# 01_MCU.net
KiCad netlist of a schematic drawn in Altium Designer
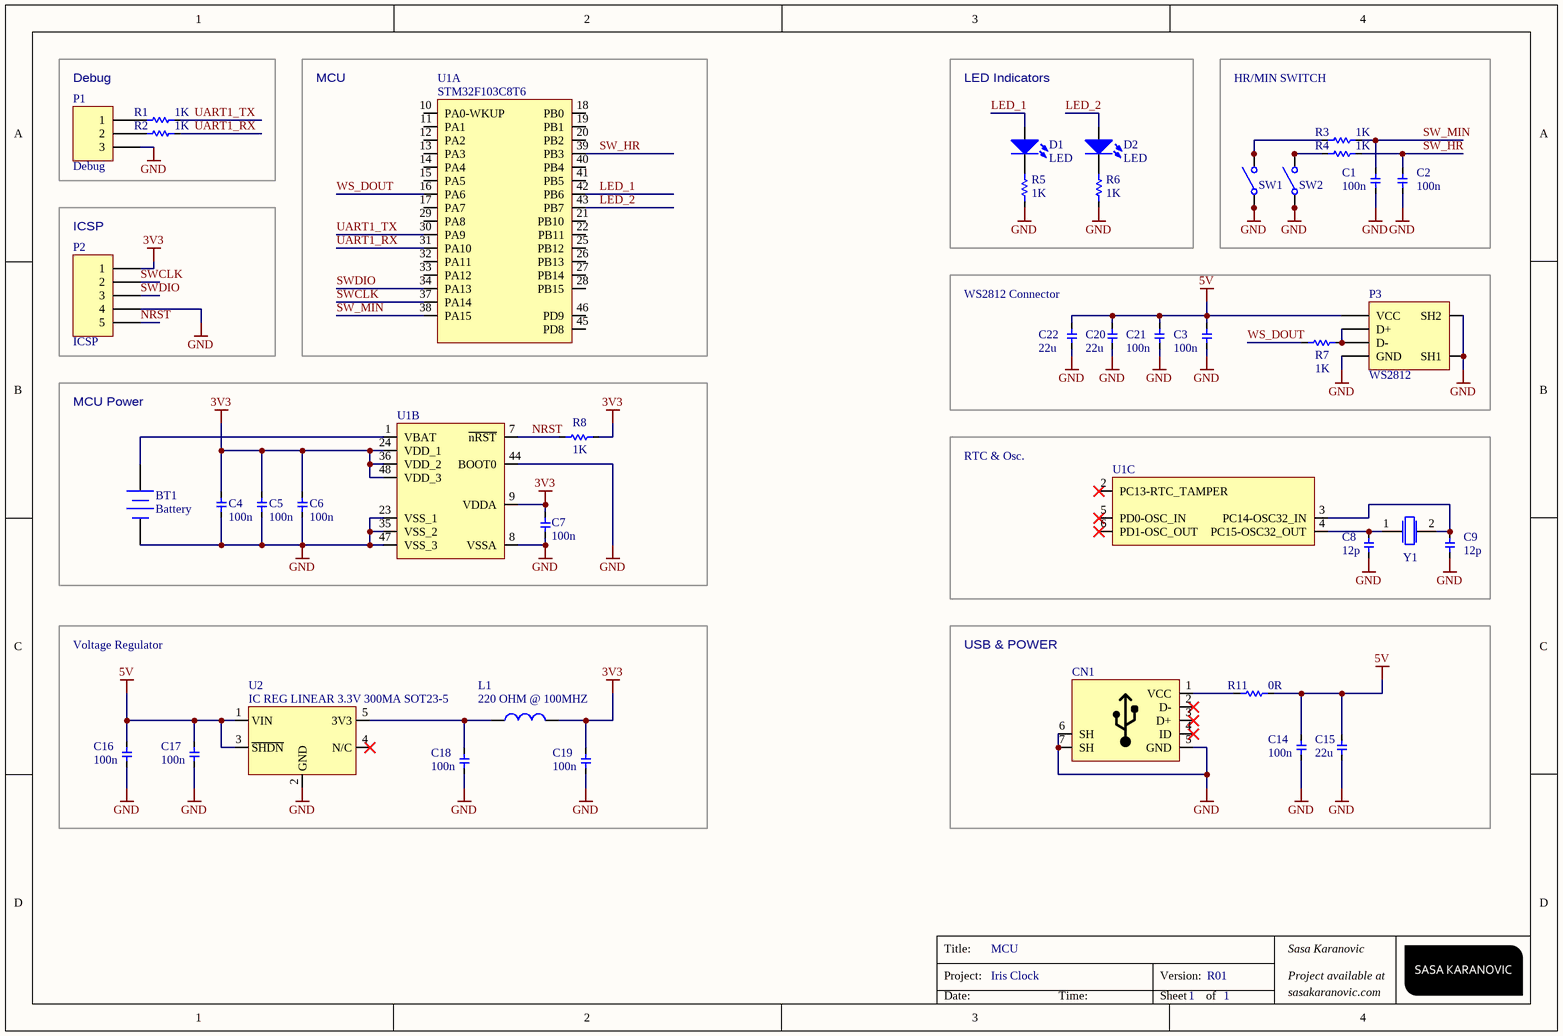
[diagram p0: 01_MCU.SchDoc]

(export (version "E")
  (design (tool "Eeschema 10.0.6"))
  (components
    (comp (ref "BT1")
      (value "Battery")
      (footprint "Moji Footprintovi:CR2032 SMD")
      (description "Multicell Battery")
      (fields
        (field (name "DISTRIBUTOR PART NUMBER") "BK-883-CT-ND")
        (field (name "MANUFACTURER") "MPD (Memory Protection Devices)")
      )
      (libsource (lib "Moji Schematici") (part "Battery"))
    )
    (comp (ref "C1")
      (value "100n")
      (footprint "Moji Footprintovi:0603 - CAP")
      (description "Capacitor")
      (fields
        (field (name "MANUFACTURER") "Samsung Electro-Mechanics")
        (field (name "MANUFACTURER PART NUMBER") "CL10A104KA8NNNC")
      )
      (libsource (lib "Moji Schematici") (part "Cap"))
    )
    (comp (ref "C2")
      (value "100n")
      (footprint "Moji Footprintovi:0603 - CAP")
      (description "Capacitor")
      (fields
        (field (name "MANUFACTURER") "Samsung Electro-Mechanics")
        (field (name "MANUFACTURER PART NUMBER") "CL10A104KA8NNNC")
      )
      (libsource (lib "Moji Schematici") (part "Cap"))
    )
    (comp (ref "C3")
      (value "100n")
      (footprint "Moji Footprintovi:0603 - CAP")
      (description "Capacitor")
      (fields
        (field (name "MANUFACTURER") "Samsung Electro-Mechanics")
        (field (name "MANUFACTURER PART NUMBER") "CL10A104KA8NNNC")
      )
      (libsource (lib "Moji Schematici") (part "Cap"))
    )
    (comp (ref "C4")
      (value "100n")
      (footprint "Moji Footprintovi:0603 - CAP")
      (description "Capacitor")
      (fields
        (field (name "MANUFACTURER") "Samsung Electro-Mechanics")
        (field (name "MANUFACTURER PART NUMBER") "CL10A104KA8NNNC")
      )
      (libsource (lib "Moji Schematici") (part "Cap"))
    )
    (comp (ref "C5")
      (value "100n")
      (footprint "Moji Footprintovi:0603 - CAP")
      (description "Capacitor")
      (fields
        (field (name "MANUFACTURER") "Samsung Electro-Mechanics")
        (field (name "MANUFACTURER PART NUMBER") "CL10A104KA8NNNC")
      )
      (libsource (lib "Moji Schematici") (part "Cap"))
    )
    (comp (ref "C6")
      (value "100n")
      (footprint "Moji Footprintovi:0603 - CAP")
      (description "Capacitor")
      (fields
        (field (name "MANUFACTURER") "Samsung Electro-Mechanics")
        (field (name "MANUFACTURER PART NUMBER") "CL10A104KA8NNNC")
      )
      (libsource (lib "Moji Schematici") (part "Cap"))
    )
    (comp (ref "C7")
      (value "100n")
      (footprint "Moji Footprintovi:0603 - CAP")
      (description "Capacitor")
      (fields
        (field (name "MANUFACTURER") "Samsung Electro-Mechanics")
        (field (name "MANUFACTURER PART NUMBER") "CL10A104KA8NNNC")
      )
      (libsource (lib "Moji Schematici") (part "Cap"))
    )
    (comp (ref "C8")
      (value "12p")
      (footprint "Moji Footprintovi:0603 - CAP")
      (description "Capacitor")
      (fields
        (field (name "MANUFACTURER") "AVX Corporation")
        (field (name "MANUFACTURER PART NUMBER") "06031A120JAT4A")
      )
      (libsource (lib "Moji Schematici") (part "Cap"))
    )
    (comp (ref "C9")
      (value "12p")
      (footprint "Moji Footprintovi:0603 - CAP")
      (description "Capacitor")
      (fields
        (field (name "MANUFACTURER") "AVX Corporation")
        (field (name "MANUFACTURER PART NUMBER") "06031A120JAT4A")
      )
      (libsource (lib "Moji Schematici") (part "Cap"))
    )
    (comp (ref "C14")
      (value "100n")
      (footprint "Moji Footprintovi:0603 - CAP")
      (description "Capacitor")
      (fields
        (field (name "MANUFACTURER") "Samsung Electro-Mechanics")
        (field (name "MANUFACTURER PART NUMBER") "CL10A104KA8NNNC")
      )
      (libsource (lib "Moji Schematici") (part "Cap"))
    )
    (comp (ref "C15")
      (value "22u")
      (footprint "Moji Footprintovi:0603 - CAP")
      (description "Capacitor")
      (fields
        (field (name "MANUFACTURER") "Samsung Electro-Mechanics")
        (field (name "MANUFACTURER PART NUMBER") "CL21A226MOCLRNC")
      )
      (libsource (lib "Moji Schematici") (part "Cap"))
    )
    (comp (ref "C16")
      (value "100n")
      (footprint "Moji Footprintovi:0603 - CAP")
      (description "Capacitor")
      (fields
        (field (name "MANUFACTURER") "Samsung Electro-Mechanics")
        (field (name "MANUFACTURER PART NUMBER") "CL10A104KA8NNNC")
      )
      (libsource (lib "Moji Schematici") (part "Cap"))
    )
    (comp (ref "C17")
      (value "100n")
      (footprint "Moji Footprintovi:0603 - CAP")
      (description "Capacitor")
      (fields
        (field (name "MANUFACTURER") "Samsung Electro-Mechanics")
        (field (name "MANUFACTURER PART NUMBER") "CL10A104KA8NNNC")
      )
      (libsource (lib "Moji Schematici") (part "Cap"))
    )
    (comp (ref "C18")
      (value "100n")
      (footprint "Moji Footprintovi:0603 - CAP")
      (description "Capacitor")
      (fields
        (field (name "MANUFACTURER") "Samsung Electro-Mechanics")
        (field (name "MANUFACTURER PART NUMBER") "CL10A104KA8NNNC")
      )
      (libsource (lib "Moji Schematici") (part "Cap"))
    )
    (comp (ref "C19")
      (value "100n")
      (footprint "Moji Footprintovi:0603 - CAP")
      (description "Capacitor")
      (fields
        (field (name "MANUFACTURER") "Samsung Electro-Mechanics")
        (field (name "MANUFACTURER PART NUMBER") "CL10A104KA8NNNC")
      )
      (libsource (lib "Moji Schematici") (part "Cap"))
    )
    (comp (ref "C20")
      (value "22u")
      (footprint "Moji Footprintovi:0805")
      (description "Capacitor")
      (fields
        (field (name "MANUFACTURER") "Samsung Electro-Mechanics")
        (field (name "MANUFACTURER PART NUMBER") "CL21A226MOCLRNC")
      )
      (libsource (lib "Moji Schematici") (part "Cap"))
    )
    (comp (ref "C21")
      (value "100n")
      (footprint "Moji Footprintovi:0603 - CAP")
      (description "Capacitor")
      (fields
        (field (name "MANUFACTURER") "Samsung Electro-Mechanics")
        (field (name "MANUFACTURER PART NUMBER") "CL10A104KA8NNNC")
      )
      (libsource (lib "Moji Schematici") (part "Cap"))
    )
    (comp (ref "C22")
      (value "22u")
      (footprint "Moji Footprintovi:0805")
      (description "Capacitor")
      (fields
        (field (name "MANUFACTURER") "Samsung Electro-Mechanics")
        (field (name "MANUFACTURER PART NUMBER") "CL21A226MOCLRNC")
      )
      (libsource (lib "Moji Schematici") (part "Cap"))
    )
    (comp (ref "CN1")
      (value "USB Connector")
      (footprint "Moji Footprintovi:Amphenol FCI 10118192-0001LF")
      (description "CONN USB MICRO B RECPT SMT R/A")
      (fields
        (field (name "MANUFACTURER") "Amphenol FCI")
        (field (name "DISTRIBUTOR PART NUMBER") "609-4613-1-ND")
      )
      (libsource (lib "Moji Schematici") (part "Amphenol FCI 10118192-0001LF"))
    )
    (comp (ref "D1")
      (value "LED")
      (footprint "Moji Footprintovi:0603 Diode")
      (description "Typical RED GaAs LED")
      (fields
        (field (name "DISTRIBUTOR PART NUMBER") "1830-1064-1-ND")
        (field (name "MANUFACTURER") "Inolux")
      )
      (libsource (lib "Moji Schematici") (part "LED"))
    )
    (comp (ref "D2")
      (value "LED")
      (footprint "Moji Footprintovi:0603 Diode")
      (description "Typical RED GaAs LED")
      (fields
        (field (name "DISTRIBUTOR PART NUMBER") "475-2832-1-ND")
        (field (name "MANUFACTURER") "OSRAM Opto Semiconductors Inc.")
      )
      (libsource (lib "Moji Schematici") (part "LED"))
    )
    (comp (ref "L1")
      (value "220 OHM @ 100MHZ")
      (footprint "Moji Footprintovi:0603")
      (description "FERRITE BEAD 220 OHM 0603 1LN")
      (fields
        (field (name "DISTRIBUTOR PART NUMBER") "490-5221-1-ND")
        (field (name "MANUFACTURER") "Murata Electronics North America")
      )
      (libsource (lib "Moji Schematici") (part "Inductor"))
    )
    (comp (ref "P1")
      (value "Debug")
      (footprint "Moji Footprintovi:Header 3x1 SMD")
      (description "Header, 3-Pin")
      (libsource (lib "Moji Schematici") (part "Header 3"))
    )
    (comp (ref "P2")
      (value "ICSP")
      (footprint "Moji Footprintovi:Header 5x1 SMD")
      (description "Header, 5-Pin")
      (libsource (lib "Moji Schematici") (part "Header 5"))
    )
    (comp (ref "P3")
      (value "WS2812")
      (footprint "Moji Footprintovi:USB Mini SMD TOP")
      (description "CONN MINI USB RCPT RA TYPE B SMD")
      (fields
        (field (name "MANUFACTURER") "EDAC Inc.")
        (field (name "MANUFACTURER PART NUMBER") "690-005-299-043")
      )
      (libsource (lib "Moji Schematici") (part "USB Connector"))
    )
    (comp (ref "R1")
      (value "1K")
      (footprint "Moji Footprintovi:0603")
      (description "Resistor")
      (fields
        (field (name "DISTRIBUTOR PART NUMBER") "311-1.0KGRCT-ND")
        (field (name "MANUFACTURER") "Yageo")
      )
      (libsource (lib "Moji Schematici") (part "Res"))
    )
    (comp (ref "R2")
      (value "1K")
      (footprint "Moji Footprintovi:0603")
      (description "Resistor")
      (fields
        (field (name "DISTRIBUTOR PART NUMBER") "311-1.0KGRCT-ND")
        (field (name "MANUFACTURER") "Yageo")
      )
      (libsource (lib "Moji Schematici") (part "Res"))
    )
    (comp (ref "R3")
      (value "1K")
      (footprint "Moji Footprintovi:0603")
      (description "Resistor")
      (fields
        (field (name "DISTRIBUTOR PART NUMBER") "311-1.0KGRCT-ND")
        (field (name "MANUFACTURER") "Yageo")
      )
      (libsource (lib "Moji Schematici") (part "Res"))
    )
    (comp (ref "R4")
      (value "1K")
      (footprint "Moji Footprintovi:0603")
      (description "Resistor")
      (fields
        (field (name "DISTRIBUTOR PART NUMBER") "311-1.0KGRCT-ND")
        (field (name "MANUFACTURER") "Yageo")
      )
      (libsource (lib "Moji Schematici") (part "Res"))
    )
    (comp (ref "R5")
      (value "1K")
      (footprint "Moji Footprintovi:0603")
      (description "Resistor")
      (fields
        (field (name "DISTRIBUTOR PART NUMBER") "311-1.0KGRCT-ND")
        (field (name "MANUFACTURER") "Yageo")
      )
      (libsource (lib "Moji Schematici") (part "Res"))
    )
    (comp (ref "R6")
      (value "1K")
      (footprint "Moji Footprintovi:0603")
      (description "Resistor")
      (fields
        (field (name "DISTRIBUTOR PART NUMBER") "311-1.0KGRCT-ND")
        (field (name "MANUFACTURER") "Yageo")
      )
      (libsource (lib "Moji Schematici") (part "Res"))
    )
    (comp (ref "R7")
      (value "1K")
      (footprint "Moji Footprintovi:0603")
      (description "Resistor")
      (fields
        (field (name "DISTRIBUTOR PART NUMBER") "311-1.0KGRCT-ND")
        (field (name "MANUFACTURER") "Yageo")
      )
      (libsource (lib "Moji Schematici") (part "Res"))
    )
    (comp (ref "R8")
      (value "1K")
      (footprint "Moji Footprintovi:0603")
      (description "Resistor")
      (fields
        (field (name "DISTRIBUTOR PART NUMBER") "311-1.0KGRCT-ND")
        (field (name "MANUFACTURER") "Yageo")
      )
      (libsource (lib "Moji Schematici") (part "Res"))
    )
    (comp (ref "R11")
      (value "0R")
      (footprint "Moji Footprintovi:0603")
      (description "Resistor")
      (fields (field (name "DISTRIBUTOR PART NUMBER") "311-0.0GRCT-ND") (field (name "MANUFACTURER") "Yageo"))
      (libsource (lib "Moji Schematici") (part "Res"))
    )
    (comp (ref "SW1")
      (value "SWITCH TACTILE SPST-NO 0.05A 12V")
      (footprint "Moji Footprintovi:PTS645")
      (fields
        (field (name "DISTRIBUTOR PART NUMBER") "CKN9088CT-ND")
        (field (name "MANUFACTURER") "C&K")
        (field (name "MANUFACTURER PART NUMBER") "PTS645SL50SMTR92 LFS")
      )
      (libsource (lib "Moji Schematici") (part "PTS645SL50SMTR92 LFS"))
    )
    (comp (ref "SW2")
      (value "SWITCH TACTILE SPST-NO 0.05A 12V")
      (footprint "Moji Footprintovi:PTS645")
      (fields
        (field (name "DISTRIBUTOR PART NUMBER") "CKN9088CT-ND")
        (field (name "MANUFACTURER") "C&K")
        (field (name "MANUFACTURER PART NUMBER") "PTS645SL50SMTR92 LFS")
      )
      (libsource (lib "Moji Schematici") (part "PTS645SL50SMTR92 LFS"))
    )
    (comp (ref "U1")
      (value "IC MCU 32BIT 64KB FLASH 48LQFP")
      (footprint "Moji Footprintovi:LQFP48_7x7mm")
      (description "IC MCU 32BIT 64KB FLASH 48LQFP")
      (fields
        (field (name "DISTRIBUTOR PART NUMBER") "497-6063-ND")
        (field (name "MANUFACTURER") "STMicroelectronics")
        (field (name "MANUFACTURER PART NUMBER") "STM32F103C8T6")
      )
      (libsource (lib "Moji Schematici") (part "STM32F103C8T6"))
    )
    (comp (ref "U2")
      (value "IC REG LINEAR 3.3V 300MA SOT23-5")
      (footprint "Moji Footprintovi:SOT-23-5")
      (fields
        (field (name "DISTRIBUTOR PART NUMBER") "AP2127K-3.3TRG1DICT-ND")
        (field (name "MANUFACTURER") "Diodes Incorporated")
        (field (name "MANUFACTURER PART NUMBER") "AP2127K-3.3TRG1")
      )
      (libsource (lib "Moji Schematici") (part "AP2127K-3.3TRG1"))
    )
    (comp (ref "Y1")
      (value "32.7680KHZ 6PF SMD")
      (footprint "Moji Footprintovi:ABS07-120")
      (description "CRYSTAL 32.7680KHZ 6PF SMD")
      (fields
        (field (name "DISTRIBUTOR PART NUMBER") "535-11937-1-ND")
        (field (name "MANUFACTURER") "Abracon LLC")
      )
      (libsource (lib "Moji Schematici") (part "ABS07-120-32.768KHZ-T"))
    )
  )
  (nets
    (net (code "1") (name "/LED_1") (class "Default")
      (node (ref "D1") (pin "A") (pinfunction "A_A") (pintype "passive"))
      (node (ref "U1") (pin "42") (pinfunction "PB6_42") (pintype "passive"))
    )
    (net (code "2") (name "/LED_2") (class "Default")
      (node (ref "D2") (pin "A") (pinfunction "A_A") (pintype "passive"))
      (node (ref "U1") (pin "43") (pinfunction "PB7_43") (pintype "passive"))
    )
    (net (code "3") (name "/NRST") (class "Default")
      (node (ref "P2") (pin "5") (pinfunction "5_5") (pintype "passive"))
      (node (ref "R8") (pin "2") (pinfunction "2_2") (pintype "passive"))
      (node (ref "U1") (pin "7") (pinfunction "~{nRST}_7") (pintype "passive"))
    )
    (net (code "4") (name "/SWCLK") (class "Default")
      (node (ref "P2") (pin "2") (pinfunction "2_2") (pintype "passive"))
      (node (ref "U1") (pin "37") (pinfunction "PA14_37") (pintype "passive"))
    )
    (net (code "5") (name "/SWDIO") (class "Default")
      (node (ref "P2") (pin "3") (pinfunction "3_3") (pintype "passive"))
      (node (ref "U1") (pin "34") (pinfunction "PA13_34") (pintype "passive"))
    )
    (net (code "6") (name "/SW_HR") (class "Default")
      (node (ref "C2") (pin "2") (pinfunction "2_2") (pintype "passive"))
      (node (ref "R4") (pin "1") (pinfunction "1_1") (pintype "passive"))
      (node (ref "U1") (pin "39") (pinfunction "PB3_39") (pintype "passive"))
    )
    (net (code "7") (name "/SW_MIN") (class "Default")
      (node (ref "C1") (pin "2") (pinfunction "2_2") (pintype "passive"))
      (node (ref "R3") (pin "1") (pinfunction "1_1") (pintype "passive"))
      (node (ref "U1") (pin "38") (pinfunction "PA15_38") (pintype "passive"))
    )
    (net (code "8") (name "/UART1_RX") (class "Default")
      (node (ref "R2") (pin "2") (pinfunction "2_2") (pintype "passive"))
      (node (ref "U1") (pin "31") (pinfunction "PA10_31") (pintype "passive"))
    )
    (net (code "9") (name "/UART1_TX") (class "Default")
      (node (ref "R1") (pin "2") (pinfunction "2_2") (pintype "passive"))
      (node (ref "U1") (pin "30") (pinfunction "PA9_30") (pintype "passive"))
    )
    (net (code "10") (name "/WS_DOUT") (class "Default")
      (node (ref "R7") (pin "1") (pinfunction "1_1") (pintype "passive"))
      (node (ref "U1") (pin "16") (pinfunction "PA6_16") (pintype "passive"))
    )
    (net (code "11") (name "3V3") (class "Default")
      (node (ref "C19") (pin "2") (pinfunction "2_2") (pintype "passive"))
      (node (ref "C4") (pin "2") (pinfunction "2_2") (pintype "passive"))
      (node (ref "C5") (pin "2") (pinfunction "2_2") (pintype "passive"))
      (node (ref "C6") (pin "2") (pinfunction "2_2") (pintype "passive"))
      (node (ref "C7") (pin "2") (pinfunction "2_2") (pintype "passive"))
      (node (ref "L1") (pin "2") (pinfunction "2_2") (pintype "passive"))
      (node (ref "P2") (pin "1") (pinfunction "1_1") (pintype "passive"))
      (node (ref "R8") (pin "1") (pinfunction "1_1") (pintype "passive"))
      (node (ref "U1") (pin "24") (pinfunction "VDD_1_24") (pintype "passive"))
      (node (ref "U1") (pin "36") (pinfunction "VDD_2_36") (pintype "passive"))
      (node (ref "U1") (pin "48") (pinfunction "VDD_3_48") (pintype "passive"))
      (node (ref "U1") (pin "9") (pinfunction "VDDA_9") (pintype "passive"))
    )
    (net (code "12") (name "5V") (class "Default")
      (node (ref "C14") (pin "2") (pinfunction "2_2") (pintype "passive"))
      (node (ref "C15") (pin "2") (pinfunction "2_2") (pintype "passive"))
      (node (ref "C16") (pin "2") (pinfunction "2_2") (pintype "passive"))
      (node (ref "C17") (pin "2") (pinfunction "2_2") (pintype "passive"))
      (node (ref "C20") (pin "2") (pinfunction "2_2") (pintype "passive"))
      (node (ref "C21") (pin "2") (pinfunction "2_2") (pintype "passive"))
      (node (ref "C22") (pin "2") (pinfunction "2_2") (pintype "passive"))
      (node (ref "C3") (pin "2") (pinfunction "2_2") (pintype "passive"))
      (node (ref "P3") (pin "VCC") (pinfunction "VCC_VCC") (pintype "passive"))
      (node (ref "R11") (pin "2") (pinfunction "2_2") (pintype "passive"))
      (node (ref "U2") (pin "1") (pinfunction "VIN_1") (pintype "passive"))
      (node (ref "U2") (pin "3") (pinfunction "~{SHDN}_3") (pintype "passive"))
    )
    (net (code "13") (name "GND") (class "Default")
      (node (ref "BT1") (pin "2") (pinfunction "-_2") (pintype "passive"))
      (node (ref "C1") (pin "1") (pinfunction "1_1") (pintype "passive"))
      (node (ref "C14") (pin "1") (pinfunction "1_1") (pintype "passive"))
      (node (ref "C15") (pin "1") (pinfunction "1_1") (pintype "passive"))
      (node (ref "C16") (pin "1") (pinfunction "1_1") (pintype "passive"))
      (node (ref "C17") (pin "1") (pinfunction "1_1") (pintype "passive"))
      (node (ref "C18") (pin "1") (pinfunction "1_1") (pintype "passive"))
      (node (ref "C19") (pin "1") (pinfunction "1_1") (pintype "passive"))
      (node (ref "C2") (pin "1") (pinfunction "1_1") (pintype "passive"))
      (node (ref "C20") (pin "1") (pinfunction "1_1") (pintype "passive"))
      (node (ref "C21") (pin "1") (pinfunction "1_1") (pintype "passive"))
      (node (ref "C22") (pin "1") (pinfunction "1_1") (pintype "passive"))
      (node (ref "C3") (pin "1") (pinfunction "1_1") (pintype "passive"))
      (node (ref "C4") (pin "1") (pinfunction "1_1") (pintype "passive"))
      (node (ref "C5") (pin "1") (pinfunction "1_1") (pintype "passive"))
      (node (ref "C6") (pin "1") (pinfunction "1_1") (pintype "passive"))
      (node (ref "C7") (pin "1") (pinfunction "1_1") (pintype "passive"))
      (node (ref "C8") (pin "1") (pinfunction "1_1") (pintype "passive"))
      (node (ref "C9") (pin "1") (pinfunction "1_1") (pintype "passive"))
      (node (ref "CN1") (pin "5") (pinfunction "GND_5") (pintype "passive"))
      (node (ref "CN1") (pin "6") (pinfunction "SH_6") (pintype "passive"))
      (node (ref "CN1") (pin "7") (pinfunction "SH_7") (pintype "passive"))
      (node (ref "P1") (pin "3") (pinfunction "3_3") (pintype "passive"))
      (node (ref "P2") (pin "4") (pinfunction "4_4") (pintype "passive"))
      (node (ref "P3") (pin "GND") (pinfunction "GND_GND") (pintype "passive"))
      (node (ref "P3") (pin "SH1") (pinfunction "SH1_SH1") (pintype "passive"))
      (node (ref "P3") (pin "SH2") (pinfunction "SH2_SH2") (pintype "passive"))
      (node (ref "R5") (pin "1") (pinfunction "1_1") (pintype "passive"))
      (node (ref "R6") (pin "1") (pinfunction "1_1") (pintype "passive"))
      (node (ref "SW1") (pin "1") (pinfunction "COMMON1_1") (pintype "passive"))
      (node (ref "SW1") (pin "2") (pinfunction "COMMON1_2") (pintype "passive"))
      (node (ref "SW2") (pin "1") (pinfunction "COMMON1_1") (pintype "passive"))
      (node (ref "SW2") (pin "2") (pinfunction "COMMON1_2") (pintype "passive"))
      (node (ref "U1") (pin "23") (pinfunction "VSS_1_23") (pintype "passive"))
      (node (ref "U1") (pin "35") (pinfunction "VSS_2_35") (pintype "passive"))
      (node (ref "U1") (pin "44") (pinfunction "BOOT0_44") (pintype "passive"))
      (node (ref "U1") (pin "47") (pinfunction "VSS_3_47") (pintype "passive"))
      (node (ref "U1") (pin "8") (pinfunction "VSSA_8") (pintype "passive"))
      (node (ref "U2") (pin "2") (pinfunction "GND_2") (pintype "passive"))
    )
    (net (code "14") (name "Net-(BT1-+)") (class "Default")
      (node (ref "BT1") (pin "1") (pinfunction "+_1") (pintype "passive"))
      (node (ref "U1") (pin "1") (pinfunction "VBAT_1") (pintype "passive"))
    )
    (net (code "15") (name "Net-(CN1-VCC)") (class "Default")
      (node (ref "CN1") (pin "1") (pinfunction "VCC_1") (pintype "passive"))
      (node (ref "R11") (pin "1") (pinfunction "1_1") (pintype "passive"))
    )
    (net (code "16") (name "Net-(D1-PadK)") (class "Default")
      (node (ref "D1") (pin "K") (pinfunction "K_K") (pintype "passive"))
      (node (ref "R5") (pin "2") (pinfunction "2_2") (pintype "passive"))
    )
    (net (code "17") (name "Net-(D2-PadK)") (class "Default")
      (node (ref "D2") (pin "K") (pinfunction "K_K") (pintype "passive"))
      (node (ref "R6") (pin "2") (pinfunction "2_2") (pintype "passive"))
    )
    (net (code "18") (name "Net-(P1-Pad1)") (class "Default")
      (node (ref "P1") (pin "1") (pinfunction "1_1") (pintype "passive"))
      (node (ref "R1") (pin "1") (pinfunction "1_1") (pintype "passive"))
    )
    (net (code "19") (name "Net-(P1-Pad2)") (class "Default")
      (node (ref "P1") (pin "2") (pinfunction "2_2") (pintype "passive"))
      (node (ref "R2") (pin "1") (pinfunction "1_1") (pintype "passive"))
    )
    (net (code "20") (name "Net-(P3-PadD+)") (class "Default")
      (node (ref "P3") (pin "D+") (pinfunction "D+_D+") (pintype "passive"))
      (node (ref "P3") (pin "D-") (pinfunction "D-_D-") (pintype "passive"))
      (node (ref "R7") (pin "2") (pinfunction "2_2") (pintype "passive"))
    )
    (net (code "21") (name "Net-(R3-Pad2)") (class "Default")
      (node (ref "R3") (pin "2") (pinfunction "2_2") (pintype "passive"))
      (node (ref "SW1") (pin "3") (pinfunction "COMMON2_3") (pintype "passive"))
      (node (ref "SW1") (pin "4") (pinfunction "COMMON2_4") (pintype "passive"))
    )
    (net (code "22") (name "Net-(R4-Pad2)") (class "Default")
      (node (ref "R4") (pin "2") (pinfunction "2_2") (pintype "passive"))
      (node (ref "SW2") (pin "3") (pinfunction "COMMON2_3") (pintype "passive"))
      (node (ref "SW2") (pin "4") (pinfunction "COMMON2_4") (pintype "passive"))
    )
    (net (code "23") (name "Net-(U1C-PC14-OSC32_IN)") (class "Default")
      (node (ref "C9") (pin "2") (pinfunction "2_2") (pintype "passive"))
      (node (ref "U1") (pin "3") (pinfunction "PC14-OSC32_IN_3") (pintype "passive"))
      (node (ref "Y1") (pin "2") (pinfunction "OSC2_2") (pintype "passive"))
    )
    (net (code "24") (name "Net-(U1C-PC15-OSC32_OUT)") (class "Default")
      (node (ref "C8") (pin "2") (pinfunction "2_2") (pintype "passive"))
      (node (ref "U1") (pin "4") (pinfunction "PC15-OSC32_OUT_4") (pintype "passive"))
      (node (ref "Y1") (pin "1") (pinfunction "OSC1_1") (pintype "passive"))
    )
    (net (code "25") (name "Net-(U2-3V3)") (class "Default")
      (node (ref "C18") (pin "2") (pinfunction "2_2") (pintype "passive"))
      (node (ref "L1") (pin "1") (pinfunction "1_1") (pintype "passive"))
      (node (ref "U2") (pin "5") (pinfunction "3V3_5") (pintype "passive"))
    )
    (net (code "26") (name "unconnected-(CN1-D+-Pad3)") (class "Default")
      (node (ref "CN1") (pin "3") (pinfunction "D+_3") (pintype "passive+no_connect"))
    )
    (net (code "27") (name "unconnected-(CN1-D--Pad2)") (class "Default")
      (node (ref "CN1") (pin "2") (pinfunction "D-_2") (pintype "passive+no_connect"))
    )
    (net (code "28") (name "unconnected-(CN1-ID-Pad4)") (class "Default")
      (node (ref "CN1") (pin "4") (pinfunction "ID_4") (pintype "passive+no_connect"))
    )
    (net (code "29") (name "unconnected-(U1A-PA0-WKUP-Pad10)") (class "Default")
      (node (ref "U1") (pin "10") (pinfunction "PA0-WKUP_10") (pintype "passive"))
    )
    (net (code "30") (name "unconnected-(U1A-PA1-Pad11)") (class "Default")
      (node (ref "U1") (pin "11") (pinfunction "PA1_11") (pintype "passive"))
    )
    (net (code "31") (name "unconnected-(U1A-PA2-Pad12)") (class "Default")
      (node (ref "U1") (pin "12") (pinfunction "PA2_12") (pintype "passive"))
    )
    (net (code "32") (name "unconnected-(U1A-PA3-Pad13)") (class "Default")
      (node (ref "U1") (pin "13") (pinfunction "PA3_13") (pintype "passive"))
    )
    (net (code "33") (name "unconnected-(U1A-PA4-Pad14)") (class "Default")
      (node (ref "U1") (pin "14") (pinfunction "PA4_14") (pintype "passive"))
    )
    (net (code "34") (name "unconnected-(U1A-PA5-Pad15)") (class "Default")
      (node (ref "U1") (pin "15") (pinfunction "PA5_15") (pintype "passive"))
    )
    (net (code "35") (name "unconnected-(U1A-PA7-Pad17)") (class "Default")
      (node (ref "U1") (pin "17") (pinfunction "PA7_17") (pintype "passive"))
    )
    (net (code "36") (name "unconnected-(U1A-PA8-Pad29)") (class "Default")
      (node (ref "U1") (pin "29") (pinfunction "PA8_29") (pintype "passive"))
    )
    (net (code "37") (name "unconnected-(U1A-PA11-Pad32)") (class "Default")
      (node (ref "U1") (pin "32") (pinfunction "PA11_32") (pintype "passive"))
    )
    (net (code "38") (name "unconnected-(U1A-PA12-Pad33)") (class "Default")
      (node (ref "U1") (pin "33") (pinfunction "PA12_33") (pintype "passive"))
    )
    (net (code "39") (name "unconnected-(U1A-PB0-Pad18)") (class "Default")
      (node (ref "U1") (pin "18") (pinfunction "PB0_18") (pintype "passive"))
    )
    (net (code "40") (name "unconnected-(U1A-PB1-Pad19)") (class "Default")
      (node (ref "U1") (pin "19") (pinfunction "PB1_19") (pintype "passive"))
    )
    (net (code "41") (name "unconnected-(U1A-PB2-Pad20)") (class "Default")
      (node (ref "U1") (pin "20") (pinfunction "PB2_20") (pintype "passive"))
    )
    (net (code "42") (name "unconnected-(U1A-PB4-Pad40)") (class "Default")
      (node (ref "U1") (pin "40") (pinfunction "PB4_40") (pintype "passive"))
    )
    (net (code "43") (name "unconnected-(U1A-PB5-Pad41)") (class "Default")
      (node (ref "U1") (pin "41") (pinfunction "PB5_41") (pintype "passive"))
    )
    (net (code "44") (name "unconnected-(U1A-PB10-Pad21)") (class "Default")
      (node (ref "U1") (pin "21") (pinfunction "PB10_21") (pintype "passive"))
    )
    (net (code "45") (name "unconnected-(U1A-PB11-Pad22)") (class "Default")
      (node (ref "U1") (pin "22") (pinfunction "PB11_22") (pintype "passive"))
    )
    (net (code "46") (name "unconnected-(U1A-PB12-Pad25)") (class "Default")
      (node (ref "U1") (pin "25") (pinfunction "PB12_25") (pintype "passive"))
    )
    (net (code "47") (name "unconnected-(U1A-PB13-Pad26)") (class "Default")
      (node (ref "U1") (pin "26") (pinfunction "PB13_26") (pintype "passive"))
    )
    (net (code "48") (name "unconnected-(U1A-PB14-Pad27)") (class "Default")
      (node (ref "U1") (pin "27") (pinfunction "PB14_27") (pintype "passive"))
    )
    (net (code "49") (name "unconnected-(U1A-PB15-Pad28)") (class "Default")
      (node (ref "U1") (pin "28") (pinfunction "PB15_28") (pintype "passive"))
    )
    (net (code "50") (name "unconnected-(U1A-PD8-Pad45)") (class "Default")
      (node (ref "U1") (pin "45") (pinfunction "PD8_45") (pintype "passive"))
    )
    (net (code "51") (name "unconnected-(U1A-PD9-Pad46)") (class "Default")
      (node (ref "U1") (pin "46") (pinfunction "PD9_46") (pintype "passive"))
    )
    (net (code "52") (name "unconnected-(U1C-PC13-RTC_TAMPER-Pad2)") (class "Default")
      (node (ref "U1") (pin "2") (pinfunction "PC13-RTC_TAMPER_2") (pintype "passive+no_connect"))
    )
    (net (code "53") (name "unconnected-(U1C-PD0-OSC_IN-Pad5)") (class "Default")
      (node (ref "U1") (pin "5") (pinfunction "PD0-OSC_IN_5") (pintype "passive+no_connect"))
    )
    (net (code "54") (name "unconnected-(U1C-PD1-OSC_OUT-Pad6)") (class "Default")
      (node (ref "U1") (pin "6") (pinfunction "PD1-OSC_OUT_6") (pintype "passive+no_connect"))
    )
    (net (code "55") (name "unconnected-(U2-N{slash}C-Pad4)") (class "Default")
      (node (ref "U2") (pin "4") (pinfunction "N/C_4") (pintype "passive+no_connect"))
    )
  )
)
